# blokadni_kondenzatori.net
KiCad netlist of a schematic drawn in Altium Designer
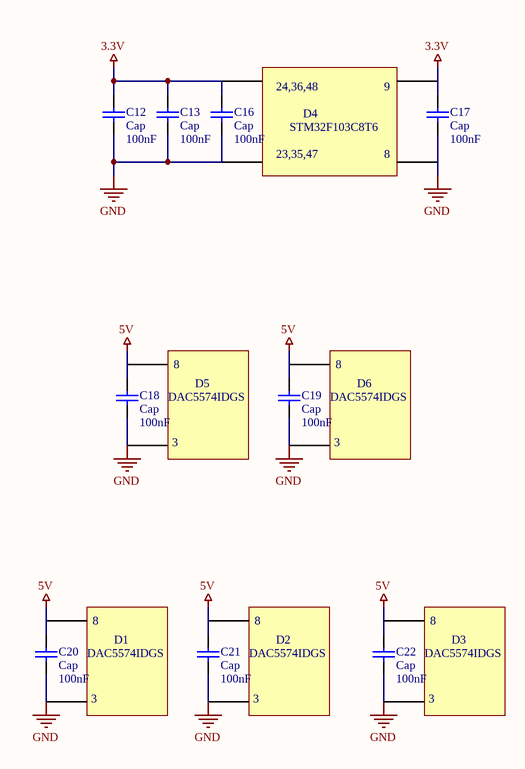
[diagram p0: blokadni_kondenzatori.SchDoc]

(export (version "E")
  (design (tool "Eeschema 10.0.6"))
  (components
    (comp (ref "C12")
      (value "Cap")
      (footprint "6-0805_L")
      (description "Capacitor")
      (fields (field (name "ALTIUM_VALUE") "100nF") (field (name "PUBLISHER") "Altium Limited"))
      (libsource (lib "Miscellaneous Devices") (part "Cap"))
    )
    (comp (ref "C13")
      (value "Cap")
      (footprint "6-0805_L")
      (description "Capacitor")
      (fields (field (name "ALTIUM_VALUE") "100nF") (field (name "PUBLISHER") "Altium Limited"))
      (libsource (lib "Miscellaneous Devices") (part "Cap"))
    )
    (comp (ref "C16")
      (value "Cap")
      (footprint "6-0805_L")
      (description "Capacitor")
      (fields (field (name "ALTIUM_VALUE") "100nF") (field (name "PUBLISHER") "Altium Limited"))
      (libsource (lib "Miscellaneous Devices") (part "Cap"))
    )
    (comp (ref "C17")
      (value "Cap")
      (footprint "6-0805_L")
      (description "Capacitor")
      (fields (field (name "ALTIUM_VALUE") "100nF") (field (name "PUBLISHER") "Altium Limited"))
      (libsource (lib "Miscellaneous Devices") (part "Cap"))
    )
    (comp (ref "C18")
      (value "Cap")
      (footprint "6-0805_L")
      (description "Capacitor")
      (fields (field (name "ALTIUM_VALUE") "100nF") (field (name "PUBLISHER") "Altium Limited"))
      (libsource (lib "Miscellaneous Devices") (part "Cap"))
    )
    (comp (ref "C19")
      (value "Cap")
      (footprint "6-0805_L")
      (description "Capacitor")
      (fields (field (name "ALTIUM_VALUE") "100nF") (field (name "PUBLISHER") "Altium Limited"))
      (libsource (lib "Miscellaneous Devices") (part "Cap"))
    )
    (comp (ref "C20")
      (value "Cap")
      (footprint "6-0805_L")
      (description "Capacitor")
      (fields (field (name "ALTIUM_VALUE") "100nF") (field (name "PUBLISHER") "Altium Limited"))
      (libsource (lib "Miscellaneous Devices") (part "Cap"))
    )
    (comp (ref "C21")
      (value "Cap")
      (footprint "6-0805_L")
      (description "Capacitor")
      (fields (field (name "ALTIUM_VALUE") "100nF") (field (name "PUBLISHER") "Altium Limited"))
      (libsource (lib "Miscellaneous Devices") (part "Cap"))
    )
    (comp (ref "C22")
      (value "Cap")
      (footprint "6-0805_L")
      (description "Capacitor")
      (fields (field (name "ALTIUM_VALUE") "100nF") (field (name "PUBLISHER") "Altium Limited"))
      (libsource (lib "Miscellaneous Devices") (part "Cap"))
    )
  )
  (nets
    (net (code "1") (name "3.3V") (class "Default")
      (node (ref "C12") (pin "2") (pinfunction "2_2") (pintype "passive"))
      (node (ref "C13") (pin "2") (pinfunction "2_2") (pintype "passive"))
      (node (ref "C16") (pin "2") (pinfunction "2_2") (pintype "passive"))
      (node (ref "C17") (pin "2") (pinfunction "2_2") (pintype "passive"))
    )
    (net (code "2") (name "5V") (class "Default")
      (node (ref "C18") (pin "2") (pinfunction "2_2") (pintype "passive"))
      (node (ref "C19") (pin "2") (pinfunction "2_2") (pintype "passive"))
      (node (ref "C20") (pin "2") (pinfunction "2_2") (pintype "passive"))
      (node (ref "C21") (pin "2") (pinfunction "2_2") (pintype "passive"))
      (node (ref "C22") (pin "2") (pinfunction "2_2") (pintype "passive"))
    )
    (net (code "3") (name "GND") (class "Default")
      (node (ref "C12") (pin "1") (pinfunction "1_1") (pintype "passive"))
      (node (ref "C13") (pin "1") (pinfunction "1_1") (pintype "passive"))
      (node (ref "C16") (pin "1") (pinfunction "1_1") (pintype "passive"))
      (node (ref "C17") (pin "1") (pinfunction "1_1") (pintype "passive"))
      (node (ref "C18") (pin "1") (pinfunction "1_1") (pintype "passive"))
      (node (ref "C19") (pin "1") (pinfunction "1_1") (pintype "passive"))
      (node (ref "C20") (pin "1") (pinfunction "1_1") (pintype "passive"))
      (node (ref "C21") (pin "1") (pinfunction "1_1") (pintype "passive"))
      (node (ref "C22") (pin "1") (pinfunction "1_1") (pintype "passive"))
    )
  )
)
